# MA2400_P2_MODUAL.net
KiCad netlist of a schematic drawn in Altium Designer
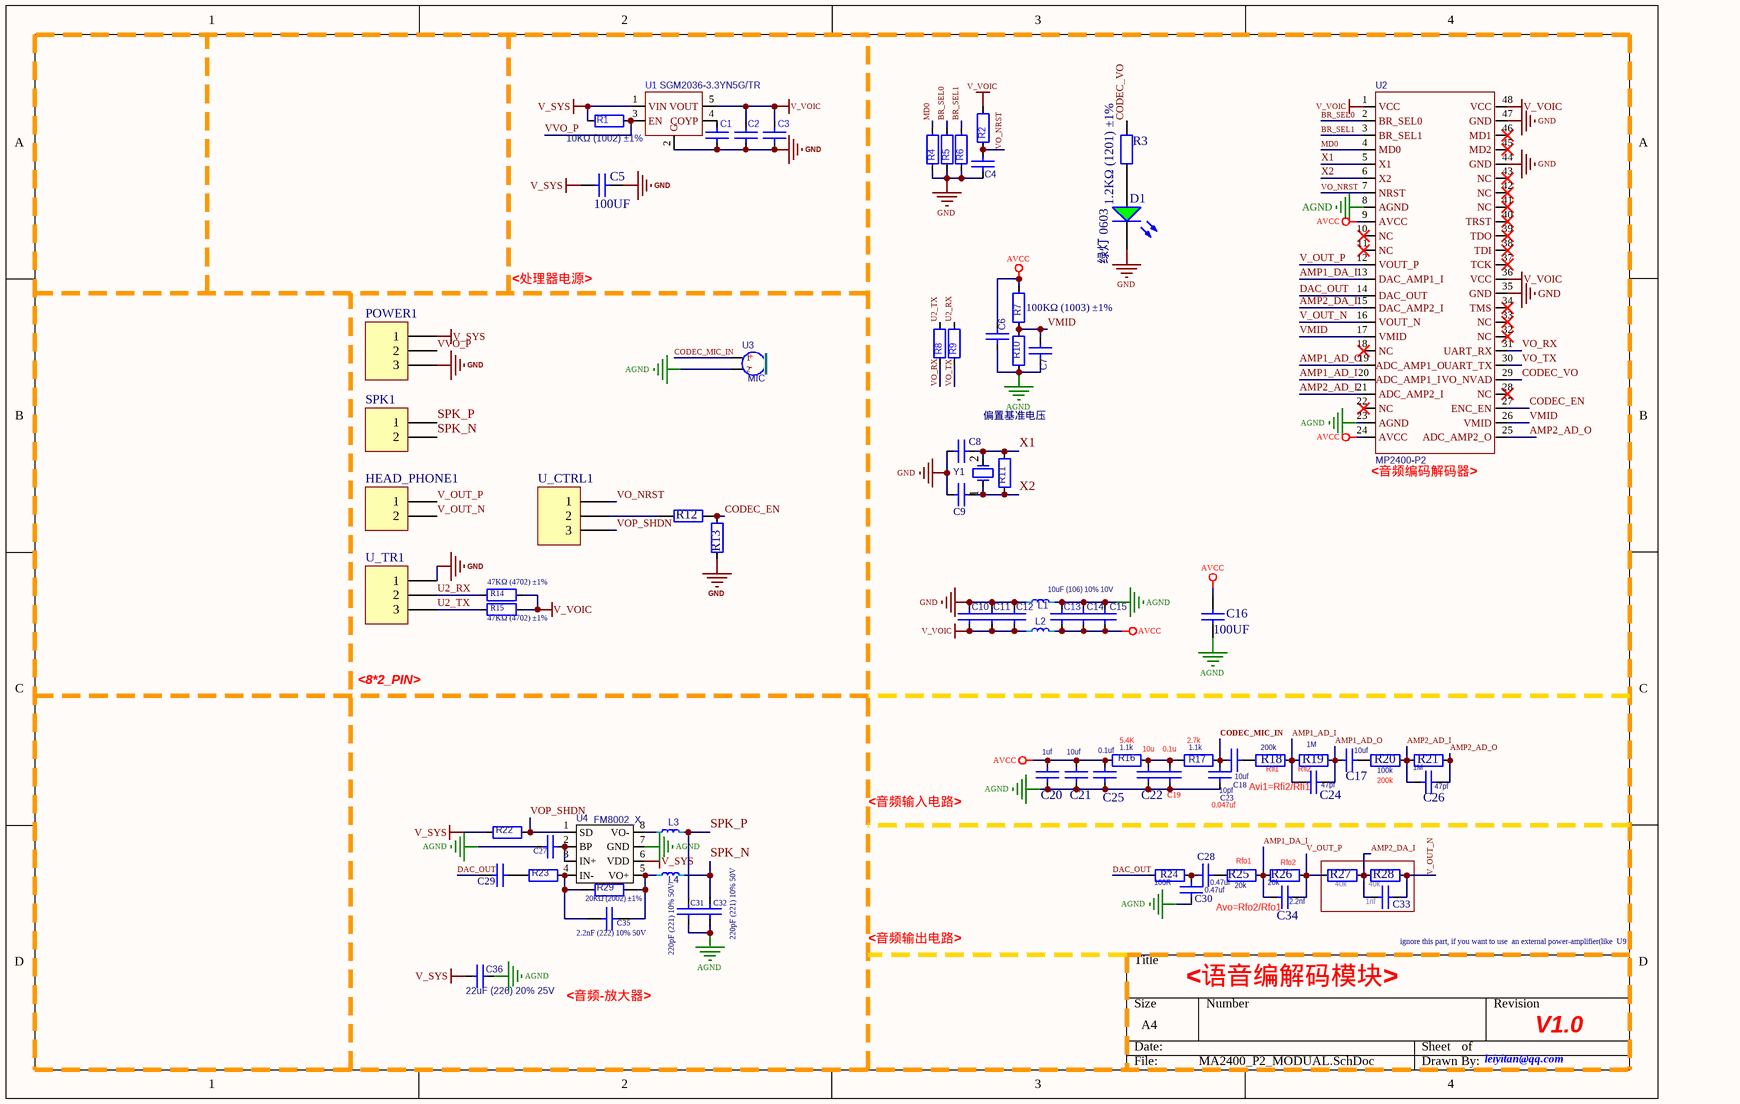
[diagram p0: MA2400_P2_MODUAL.SchDoc]

(export (version "E")
  (design (tool "Eeschema 10.0.6"))
  (components
    (comp (ref "C1")
      (value "100nF (104) 10% 16V")
      (footprint "0402_C")
      (description "贴片电容")
      (libsource (lib "Miscellaneous Devices LC") (part "0402 100nF (104) 10% 16V"))
    )
    (comp (ref "C2")
      (value "100nF (104) 10% 16V")
      (footprint "0402_C")
      (description "贴片电容")
      (libsource (lib "Miscellaneous Devices LC") (part "0402 100nF (104) 10% 16V"))
    )
    (comp (ref "C3")
      (value "10uF (106) 10% 10V")
      (footprint "0603_C")
      (description "贴片电容")
      (libsource (lib "Miscellaneous Devices LC") (part "0603 10uF (106) 10% 10V"))
    )
    (comp (ref "C4")
      (value "10uF (106) 20% 6.3V")
      (footprint "0402_C")
      (description "贴片电容")
      (libsource (lib "Miscellaneous Devices LC") (part "0402 10uF (106) 20% 6.3V"))
    )
    (comp (ref "C5")
      (value "100UF")
      (footprint "C1210")
      (description "贴片钽电容")
      (libsource (lib "Miscellaneous Devices LC") (part "1206 10uF (106) 10% 50V"))
    )
    (comp (ref "C6")
      (value "1.0uF (105) 10% 25V")
      (footprint "0402_C")
      (description "贴片电容")
      (libsource (lib "Miscellaneous Devices LC") (part "0402 1.0uF (105) 10% 25V"))
    )
    (comp (ref "C7")
      (value "1.0uF (105) 10% 25V")
      (footprint "0402_C")
      (description "贴片电容")
      (libsource (lib "Miscellaneous Devices LC") (part "0402 1.0uF (105) 10% 25V"))
    )
    (comp (ref "C8")
      (value "12pF (120) 5% 50V")
      (footprint "0603_C")
      (description "贴片电容")
      (libsource (lib "Miscellaneous Devices LC") (part "0603 12pF (120) 5% 50V"))
    )
    (comp (ref "C9")
      (value "12pF (120) 5% 50V")
      (footprint "0603_C")
      (description "贴片电容")
      (libsource (lib "Miscellaneous Devices LC") (part "0603 12pF (120) 5% 50V"))
    )
    (comp (ref "C10")
      (value "100nF (104) 10% 16V")
      (footprint "0402_C")
      (description "贴片电容")
      (libsource (lib "Miscellaneous Devices LC") (part "0402 100nF (104) 10% 16V"))
    )
    (comp (ref "C11")
      (value "100nF (104) 10% 16V")
      (footprint "0402_C")
      (description "贴片电容")
      (libsource (lib "Miscellaneous Devices LC") (part "0402 100nF (104) 10% 16V"))
    )
    (comp (ref "C12")
      (value "100nF (104) 10% 16V")
      (footprint "0402_C")
      (description "贴片电容")
      (libsource (lib "Miscellaneous Devices LC") (part "0402 100nF (104) 10% 16V"))
    )
    (comp (ref "C13")
      (value "10uF (106) 10% 10V")
      (footprint "0603_C")
      (description "贴片电容")
      (libsource (lib "Miscellaneous Devices LC") (part "0603 10uF (106) 10% 10V"))
    )
    (comp (ref "C14")
      (value "100nF (104) 10% 16V")
      (footprint "0402_C")
      (description "贴片电容")
      (libsource (lib "Miscellaneous Devices LC") (part "0402 100nF (104) 10% 16V"))
    )
    (comp (ref "C15")
      (value "100nF (104) 10% 16V")
      (footprint "0402_C")
      (description "贴片电容")
      (libsource (lib "Miscellaneous Devices LC") (part "0402 100nF (104) 10% 16V"))
    )
    (comp (ref "C16")
      (value "100UF")
      (footprint "C1210")
      (description "贴片钽电容")
      (libsource (lib "Miscellaneous Devices LC") (part "1206 10uF (106) 10% 50V"))
    )
    (comp (ref "C17")
      (value "10uF (106) 10% 25V")
      (footprint "0805_C")
      (description "贴片电容")
      (libsource (lib "Miscellaneous Devices LC") (part "0805 10uF (106) 10% 25V"))
    )
    (comp (ref "C18")
      (value "10uF (106) 10% 25V")
      (footprint "0805_C")
      (description "贴片电容")
      (libsource (lib "Miscellaneous Devices LC") (part "0805 10uF (106) 10% 25V"))
    )
    (comp (ref "C19")
      (value "47nF (473) 10% 50V")
      (footprint "0805_C")
      (description "贴片电容")
      (libsource (lib "Miscellaneous Devices LC") (part "0805 47nF (473) 10% 50V"))
    )
    (comp (ref "C20")
      (value "1uF (105) 10% 50V")
      (footprint "0805_C")
      (description "贴片电容")
      (libsource (lib "Miscellaneous Devices LC") (part "0805 1uF (105) 10% 50V"))
    )
    (comp (ref "C21")
      (value "10uF (106) 10% 25V")
      (footprint "0805_C")
      (description "贴片电容")
      (libsource (lib "Miscellaneous Devices LC") (part "0805 10uF (106) 10% 25V"))
    )
    (comp (ref "C22")
      (value "47nF (473) 10% 50V")
      (footprint "0805_C")
      (description "贴片电容")
      (libsource (lib "Miscellaneous Devices LC") (part "0805 47nF (473) 10% 50V"))
    )
    (comp (ref "C23")
      (value "10pF (100) 5% 50V")
      (footprint "0603_C")
      (description "贴片电容")
      (libsource (lib "Miscellaneous Devices LC") (part "0603 10pF (100) 5% 50V"))
    )
    (comp (ref "C24")
      (value "47pF (470) 5% 50V")
      (footprint "0805_C")
      (description "贴片电容")
      (libsource (lib "Miscellaneous Devices LC") (part "0805 47pF (470) 5% 50V"))
    )
    (comp (ref "C25")
      (value "100nF(104) 10% 50V")
      (footprint "0805_C")
      (description "贴片电容")
      (libsource (lib "Miscellaneous Devices LC") (part "0805 100nF(104) 10% 50V"))
    )
    (comp (ref "C26")
      (value "47pF (470) 5% 50V")
      (footprint "0805_C")
      (description "贴片电容")
      (libsource (lib "Miscellaneous Devices LC") (part "0805 47pF (470) 5% 50V"))
    )
    (comp (ref "C27")
      (value "1uF (105) 10% 50V")
      (footprint "0805_C")
      (description "贴片电容")
      (libsource (lib "Miscellaneous Devices LC") (part "0805 1uF (105) 10% 50V"))
    )
    (comp (ref "C28")
      (value "470nF (474) 10% 50V")
      (footprint "0805_C")
      (description "贴片电容")
      (libsource (lib "") (part "0805 470nF (474) 10% 50V_1"))
    )
    (comp (ref "C29")
      (value "470nF (474) 10% 50V")
      (footprint "0805_C")
      (description "贴片电容")
      (libsource (lib "Miscellaneous Devices LC") (part "0805 470nF (474) 10% 50V"))
    )
    (comp (ref "C30")
      (value "470nF (474) 10% 50V")
      (footprint "0805_C")
      (description "贴片电容")
      (libsource (lib "") (part "0805 470nF (474) 10% 50V_1"))
    )
    (comp (ref "C31")
      (value "220pF (221) 10% 50V")
      (footprint "0402_C")
      (description "贴片电容")
      (libsource (lib "Miscellaneous Devices LC") (part "0402 220pF (221) 10% 50V"))
    )
    (comp (ref "C32")
      (value "220pF (221) 10% 50V")
      (footprint "0402_C")
      (description "贴片电容")
      (libsource (lib "Miscellaneous Devices LC") (part "0402 220pF (221) 10% 50V"))
    )
    (comp (ref "C33")
      (value "1nF (102) 10% 50V")
      (footprint "0805_C")
      (description "贴片电容")
      (libsource (lib "Miscellaneous Devices LC") (part "0805 1nF (102) 10% 50V"))
    )
    (comp (ref "C34")
      (value "2.2nF (222) 5% 50V")
      (footprint "0805_C")
      (description "贴片电容")
      (libsource (lib "Miscellaneous Devices LC") (part "0805 2.2nF (222) 5% 50V"))
    )
    (comp (ref "C35")
      (value "2.2nF (222) 10% 50V")
      (footprint "0603_C")
      (description "贴片电容")
      (libsource (lib "Miscellaneous Devices LC") (part "0603 2.2nF (222) 10% 50V"))
    )
    (comp (ref "C36")
      (value "22uF (226) 20% 25V")
      (footprint "0805_C")
      (description "贴片电容")
      (libsource (lib "Miscellaneous Devices LC") (part "0805 22uF (226) 20% 25V"))
    )
    (comp (ref "D1")
      (value "绿灯 0603")
      (footprint "0603_LED_S1")
      (description "发光二极管")
      (libsource (lib "Miscellaneous Devices LC") (part "0603 绿灯"))
    )
    (comp (ref "HEAD_PHONE1")
      (value "~")
      (footprint "HDR1X2")
      (description "Header, 2-Pin")
      (fields (field (name "PUBLISHER") "Altium Limited"))
      (libsource (lib "Miscellaneous Connectors") (part "Header 2"))
    )
    (comp (ref "L1")
      (value "10uH ±10%")
      (footprint "0603_L")
      (description "贴片电感")
      (libsource (lib "ZGB_Sta_Prj") (part "BEAD"))
    )
    (comp (ref "L2")
      (value "10uH ±10%")
      (footprint "0603_L")
      (description "贴片电感")
      (libsource (lib "ZGB_Sta_Prj") (part "BEAD"))
    )
    (comp (ref "L3")
      (value "10uH ±10%")
      (footprint "0603_L")
      (description "贴片电感")
      (libsource (lib "ZGB_Sta_Prj") (part "BEAD"))
    )
    (comp (ref "L4")
      (value "10uH ±10%")
      (footprint "0603_L")
      (description "贴片电感")
      (libsource (lib "ZGB_Sta_Prj") (part "BEAD"))
    )
    (comp (ref "POWER1")
      (value "~")
      (footprint "HDR1X3")
      (description "Header, 3-Pin")
      (fields (field (name "PUBLISHER") "Altium Limited"))
      (libsource (lib "Miscellaneous Connectors") (part "Header 3"))
    )
    (comp (ref "R1")
      (value "10KΩ (1002) ±1%")
      (footprint "0402_R")
      (description "贴片电阻")
      (libsource (lib "") (part "0402 10KΩ (1002) 1%_2"))
    )
    (comp (ref "R2")
      (value "10KΩ (1002) ±1%")
      (footprint "0402_R")
      (description "贴片电阻")
      (libsource (lib "Miscellaneous Devices LC") (part "0402 10KΩ (1002) 1%"))
    )
    (comp (ref "R3")
      (value "1.2KΩ (1201) ±1%")
      (footprint "0402_R")
      (description "贴片电阻")
      (libsource (lib "Miscellaneous Devices LC") (part "0402 1.2KΩ (1201) 1%"))
    )
    (comp (ref "R4")
      (value "10KΩ (1002) ±1%")
      (footprint "0402_R")
      (description "贴片电阻")
      (libsource (lib "Miscellaneous Devices LC") (part "0402 10KΩ (1002) 1%"))
    )
    (comp (ref "R5")
      (value "10KΩ (1002) ±1%")
      (footprint "0402_R")
      (description "贴片电阻")
      (libsource (lib "Miscellaneous Devices LC") (part "0402 10KΩ (1002) 1%"))
    )
    (comp (ref "R6")
      (value "10KΩ (1002) ±1%")
      (footprint "0402_R")
      (description "贴片电阻")
      (libsource (lib "Miscellaneous Devices LC") (part "0402 10KΩ (1002) 1%"))
    )
    (comp (ref "R7")
      (value "100KΩ (1003) ±1%")
      (footprint "0402_R")
      (description "贴片电阻")
      (libsource (lib "Miscellaneous Devices LC") (part "0402 100KΩ (1003) 1%"))
    )
    (comp (ref "R8")
      (value "10KΩ (1002) ±1%")
      (footprint "0402_R")
      (description "贴片电阻")
      (libsource (lib "Miscellaneous Devices LC") (part "0402 10KΩ (1002) 1%"))
    )
    (comp (ref "R9")
      (value "10KΩ (1002) ±1%")
      (footprint "0402_R")
      (description "贴片电阻")
      (libsource (lib "Miscellaneous Devices LC") (part "0402 10KΩ (1002) 1%"))
    )
    (comp (ref "R10")
      (value "100KΩ (1003) ±1%")
      (footprint "0402_R")
      (description "贴片电阻")
      (libsource (lib "Miscellaneous Devices LC") (part "0402 100KΩ (1003) 1%"))
    )
    (comp (ref "R11")
      (value "1MΩ (1004) ±1%")
      (footprint "0402_R")
      (description "贴片电阻")
      (libsource (lib "Miscellaneous Devices LC") (part "0402 1MΩ (1004) 1%"))
    )
    (comp (ref "R12")
      (value "1KΩ (1001) ±1%")
      (footprint "0402_R")
      (description "贴片电阻")
      (libsource (lib "Miscellaneous Devices LC") (part "0402 1KΩ (1001) 1%"))
    )
    (comp (ref "R13")
      (value "10KΩ (1002) ±1%")
      (footprint "0402_R")
      (description "贴片电阻")
      (libsource (lib "") (part "0402 10KΩ (1002) 1%_1"))
    )
    (comp (ref "R14")
      (value "47KΩ (4702) ±1%")
      (footprint "0402_R")
      (description "贴片电阻")
      (libsource (lib "Miscellaneous Devices LC") (part "0402 47KΩ (4702) 1%"))
    )
    (comp (ref "R15")
      (value "47KΩ (4702) ±1%")
      (footprint "0402_R")
      (description "贴片电阻")
      (libsource (lib "Miscellaneous Devices LC") (part "0402 47KΩ (4702) 1%"))
    )
    (comp (ref "R16")
      (value "1.1KΩ (1101) ±1%")
      (footprint "0603_R")
      (description "贴片电阻")
      (libsource (lib "Miscellaneous Devices LC") (part "0603 1.1KΩ (1101) 1%"))
    )
    (comp (ref "R17")
      (value "1.1KΩ (1101) ±1%")
      (footprint "0603_R")
      (description "贴片电阻")
      (libsource (lib "Miscellaneous Devices LC") (part "0603 1.1KΩ (1101) 1%"))
    )
    (comp (ref "R18")
      (value "200KΩ (2003) ±1%")
      (footprint "0805_R")
      (description "贴片电阻")
      (libsource (lib "Miscellaneous Devices LC") (part "0805 200KΩ (2003) 1%"))
    )
    (comp (ref "R19")
      (value "1MΩ (1004) ±1%")
      (footprint "0805_R")
      (description "贴片电阻")
      (libsource (lib "Miscellaneous Devices LC") (part "0805 1MΩ (1004) 1%"))
    )
    (comp (ref "R20")
      (value "100KΩ (1003) ±1%")
      (footprint "0805_R")
      (description "贴片电阻")
      (libsource (lib "Miscellaneous Devices LC") (part "0805 100KΩ (1003) 1%"))
    )
    (comp (ref "R21")
      (value "1MΩ (1004) ±1%")
      (footprint "0805_R")
      (description "贴片电阻")
      (libsource (lib "Miscellaneous Devices LC") (part "0805 1MΩ (1004) 1%"))
    )
    (comp (ref "R22")
      (value "10KΩ (1002) ±1%")
      (footprint "0402_R")
      (description "贴片电阻")
      (libsource (lib "") (part "0402 10KΩ (1002) 1%_2"))
    )
    (comp (ref "R23")
      (value "20KΩ (2002) ±1%")
      (footprint "0402_R")
      (description "贴片电阻")
      (libsource (lib "") (part "0402 20KΩ (2002) 1%_1"))
    )
    (comp (ref "R24")
      (value "100Ω (1000) ±1%")
      (footprint "0805_R")
      (description "贴片电阻")
      (libsource (lib "Miscellaneous Devices LC") (part "0805 100Ω (1000) 1%"))
    )
    (comp (ref "R25")
      (value "20KΩ (2002) ±1%")
      (footprint "0805_R")
      (description "贴片电阻")
      (libsource (lib "Miscellaneous Devices LC") (part "0805 20KΩ (2002) 1%"))
    )
    (comp (ref "R26")
      (value "20KΩ (2002) ±1%")
      (footprint "0805_R")
      (description "贴片电阻")
      (libsource (lib "Miscellaneous Devices LC") (part "0805 20KΩ (2002) 1%"))
    )
    (comp (ref "R27")
      (value "40.2KΩ (4022) ±1%")
      (footprint "0805_R")
      (description "贴片电阻")
      (libsource (lib "Miscellaneous Devices LC") (part "0805 40.2KΩ (4022) 1%"))
    )
    (comp (ref "R28")
      (value "40.2KΩ (4022) ±1%")
      (footprint "0805_R")
      (description "贴片电阻")
      (libsource (lib "Miscellaneous Devices LC") (part "0805 40.2KΩ (4022) 1%"))
    )
    (comp (ref "R29")
      (value "20KΩ (2002) ±1%")
      (footprint "0402_R")
      (description "贴片电阻")
      (libsource (lib "Miscellaneous Devices LC") (part "0402 20KΩ (2002) 1%"))
    )
    (comp (ref "SPK1")
      (value "~")
      (footprint "HDR1X2")
      (description "Header, 2-Pin")
      (fields (field (name "PUBLISHER") "Altium Limited"))
      (libsource (lib "Miscellaneous Connectors") (part "Header 2"))
    )
    (comp (ref "U1")
      (value "SGM2036-3.3YN5G/TR")
      (footprint "SOT23-5")
      (description "3.3 LDO")
      (libsource (lib "ZGB_Sta_Prj") (part "LDO"))
    )
    (comp (ref "U2")
      (value "MP2400-P2")
      (footprint "LQFP-48_7x7x05P")
      (description "音频处理器")
      (libsource (lib "ZGB_Sta_Prj") (part "MP2400-P2"))
    )
    (comp (ref "U3")
      (value "MIC")
      (footprint "6022_MIC")
      (description "6022插针七级防水咪头7级防水麦克风咪头")
      (libsource (lib "ZGB_Sta_Prj") (part "MIC"))
    )
    (comp (ref "U4")
      (value "FM8002_X")
      (footprint "SOP-8_150mil")
      (description "音频放大器")
      (libsource (lib "ZGB_Sta_Prj") (part "FM8002_X"))
    )
    (comp (ref "U_CTRL1")
      (value "~")
      (footprint "HDR1X3")
      (description "Header, 3-Pin")
      (fields (field (name "PUBLISHER") "Altium Limited"))
      (libsource (lib "Miscellaneous Connectors") (part "Header 3"))
    )
    (comp (ref "U_TR1")
      (value "~")
      (footprint "HDR1X3")
      (description "Header, 3-Pin")
      (fields (field (name "PUBLISHER") "Altium Limited"))
      (libsource (lib "Miscellaneous Connectors") (part "Header 3"))
    )
    (comp (ref "Y1")
      (value "8MHz ±20ppm 20pF")
      (footprint "SMD-5032_2P")
      (description "贴片无源晶振/YSX530GA 8MHZ 20PF 10PPM -40~+85 编带")
      (libsource (lib "Miscellaneous Devices LC") (part "SMD-5032_2P 8MHz 20ppm 20pF"))
    )
  )
  (nets
    (net (code "1") (name "/AMP1_AD_I") (class "Default")
      (node (ref "C24") (pin "1") (pinfunction "1_1") (pintype "passive"))
      (node (ref "R18") (pin "2") (pinfunction "2_2") (pintype "passive"))
      (node (ref "R19") (pin "1") (pinfunction "1_1") (pintype "passive"))
      (node (ref "U2") (pin "20") (pinfunction "ADC_AMP1_I_20") (pintype "passive"))
    )
    (net (code "2") (name "/AMP1_AD_O") (class "Default")
      (node (ref "C17") (pin "2") (pinfunction "2_2") (pintype "passive"))
      (node (ref "C24") (pin "2") (pinfunction "2_2") (pintype "passive"))
      (node (ref "R19") (pin "2") (pinfunction "2_2") (pintype "passive"))
      (node (ref "U2") (pin "19") (pinfunction "ADC_AMP1_O_19") (pintype "passive"))
    )
    (net (code "3") (name "/AMP1_DA_I") (class "Default")
      (node (ref "C34") (pin "2") (pinfunction "2_2") (pintype "passive"))
      (node (ref "R25") (pin "2") (pinfunction "2_2") (pintype "passive"))
      (node (ref "R26") (pin "1") (pinfunction "1_1") (pintype "passive"))
      (node (ref "U2") (pin "13") (pinfunction "DAC_AMP1_I_13") (pintype "passive"))
    )
    (net (code "4") (name "/AMP2_AD_I") (class "Default")
      (node (ref "C26") (pin "1") (pinfunction "1_1") (pintype "passive"))
      (node (ref "R20") (pin "2") (pinfunction "2_2") (pintype "passive"))
      (node (ref "R21") (pin "1") (pinfunction "1_1") (pintype "passive"))
      (node (ref "U2") (pin "21") (pinfunction "ADC_AMP2_I_21") (pintype "passive"))
    )
    (net (code "5") (name "/AMP2_AD_O") (class "Default")
      (node (ref "C26") (pin "2") (pinfunction "2_2") (pintype "passive"))
      (node (ref "R21") (pin "2") (pinfunction "2_2") (pintype "passive"))
      (node (ref "U2") (pin "25") (pinfunction "ADC_AMP2_O_25") (pintype "passive"))
    )
    (net (code "6") (name "/AMP2_DA_I") (class "Default")
      (node (ref "C33") (pin "1") (pinfunction "1_1") (pintype "passive"))
      (node (ref "R27") (pin "2") (pinfunction "2_2") (pintype "passive"))
      (node (ref "R28") (pin "1") (pinfunction "1_1") (pintype "passive"))
      (node (ref "U2") (pin "15") (pinfunction "DAC_AMP2_I_15") (pintype "passive"))
    )
    (net (code "7") (name "/BR_SEL0") (class "Default")
      (node (ref "R5") (pin "2") (pinfunction "2_2") (pintype "passive"))
      (node (ref "U2") (pin "2") (pinfunction "BR_SEL0_2") (pintype "passive"))
    )
    (net (code "8") (name "/BR_SEL1") (class "Default")
      (node (ref "R6") (pin "2") (pinfunction "2_2") (pintype "passive"))
      (node (ref "U2") (pin "3") (pinfunction "BR_SEL1_3") (pintype "passive"))
    )
    (net (code "9") (name "/CODEC_EN") (class "Default")
      (node (ref "R12") (pin "2") (pinfunction "2_2") (pintype "passive"))
      (node (ref "R13") (pin "1") (pinfunction "1_1") (pintype "passive"))
      (node (ref "U2") (pin "27") (pinfunction "ENC_EN_27") (pintype "passive"))
    )
    (net (code "10") (name "/CODEC_MIC_IN") (class "Default")
      (node (ref "C18") (pin "2") (pinfunction "2_2") (pintype "passive"))
      (node (ref "C23") (pin "2") (pinfunction "2_2") (pintype "passive"))
      (node (ref "R17") (pin "2") (pinfunction "2_2") (pintype "passive"))
      (node (ref "U3") (pin "1") (pinfunction "1_1") (pintype "passive"))
    )
    (net (code "11") (name "/CODEC_VO") (class "Default")
      (node (ref "R3") (pin "2") (pinfunction "2_2") (pintype "passive"))
      (node (ref "U2") (pin "29") (pinfunction "VO_NVAD_29") (pintype "passive"))
    )
    (net (code "12") (name "/DAC_OUT") (class "Default")
      (node (ref "C29") (pin "1") (pinfunction "1_1") (pintype "passive"))
      (node (ref "R24") (pin "1") (pinfunction "1_1") (pintype "passive"))
      (node (ref "U2") (pin "14") (pinfunction "DAC_OUT_14") (pintype "passive"))
    )
    (net (code "13") (name "/MD0") (class "Default")
      (node (ref "R4") (pin "2") (pinfunction "2_2") (pintype "passive"))
      (node (ref "U2") (pin "4") (pinfunction "MD0_4") (pintype "passive"))
    )
    (net (code "14") (name "/SPK_N") (class "Default")
      (node (ref "C32") (pin "2") (pinfunction "2_2") (pintype "passive"))
      (node (ref "L4") (pin "1") (pinfunction "1_1") (pintype "passive"))
      (node (ref "SPK1") (pin "2") (pinfunction "2_2") (pintype "passive"))
    )
    (net (code "15") (name "/SPK_P") (class "Default")
      (node (ref "C31") (pin "2") (pinfunction "2_2") (pintype "passive"))
      (node (ref "L3") (pin "1") (pinfunction "1_1") (pintype "passive"))
      (node (ref "SPK1") (pin "1") (pinfunction "1_1") (pintype "passive"))
    )
    (net (code "16") (name "/U2_RX") (class "Default")
      (node (ref "R14") (pin "1") (pinfunction "1_1") (pintype "passive"))
      (node (ref "R9") (pin "2") (pinfunction "2_2") (pintype "passive"))
      (node (ref "U_TR1") (pin "2") (pinfunction "2_2") (pintype "passive"))
    )
    (net (code "17") (name "/U2_TX") (class "Default")
      (node (ref "R15") (pin "1") (pinfunction "1_1") (pintype "passive"))
      (node (ref "R8") (pin "2") (pinfunction "2_2") (pintype "passive"))
      (node (ref "U_TR1") (pin "3") (pinfunction "3_3") (pintype "passive"))
    )
    (net (code "18") (name "/VMID") (class "Default")
      (node (ref "C7") (pin "2") (pinfunction "2_2") (pintype "passive"))
      (node (ref "R10") (pin "2") (pinfunction "2_2") (pintype "passive"))
      (node (ref "R7") (pin "1") (pinfunction "1_1") (pintype "passive"))
      (node (ref "U2") (pin "17") (pinfunction "VMID_17") (pintype "passive"))
      (node (ref "U2") (pin "26") (pinfunction "VMID_26") (pintype "passive"))
    )
    (net (code "19") (name "/VOP_SHDN") (class "Default")
      (node (ref "R22") (pin "2") (pinfunction "2_2") (pintype "passive"))
      (node (ref "U4") (pin "1") (pinfunction "SD_1") (pintype "passive"))
      (node (ref "U_CTRL1") (pin "3") (pinfunction "3_3") (pintype "passive"))
    )
    (net (code "20") (name "/VO_NRST") (class "Default")
      (node (ref "C4") (pin "2") (pinfunction "2_2") (pintype "passive"))
      (node (ref "R2") (pin "1") (pinfunction "1_1") (pintype "passive"))
      (node (ref "U2") (pin "7") (pinfunction "NRST_7") (pintype "passive"))
      (node (ref "U_CTRL1") (pin "1") (pinfunction "1_1") (pintype "passive"))
    )
    (net (code "21") (name "/VO_RX") (class "Default")
      (node (ref "R8") (pin "1") (pinfunction "1_1") (pintype "passive"))
      (node (ref "U2") (pin "31") (pinfunction "UART_RX_31") (pintype "passive"))
    )
    (net (code "22") (name "/VO_TX") (class "Default")
      (node (ref "R9") (pin "1") (pinfunction "1_1") (pintype "passive"))
      (node (ref "U2") (pin "30") (pinfunction "UART_TX_30") (pintype "passive"))
    )
    (net (code "23") (name "/VVO_P") (class "Default")
      (node (ref "POWER1") (pin "2") (pinfunction "2_2") (pintype "passive"))
      (node (ref "R1") (pin "2") (pinfunction "2_2") (pintype "passive"))
      (node (ref "U1") (pin "3") (pinfunction "EN_3") (pintype "passive"))
    )
    (net (code "24") (name "/V_OUT_N") (class "Default")
      (node (ref "C33") (pin "2") (pinfunction "2_2") (pintype "passive"))
      (node (ref "HEAD_PHONE1") (pin "2") (pinfunction "2_2") (pintype "passive"))
      (node (ref "R28") (pin "2") (pinfunction "2_2") (pintype "passive"))
      (node (ref "U2") (pin "16") (pinfunction "VOUT_N_16") (pintype "passive"))
    )
    (net (code "25") (name "/V_OUT_P") (class "Default")
      (node (ref "C34") (pin "1") (pinfunction "1_1") (pintype "passive"))
      (node (ref "HEAD_PHONE1") (pin "1") (pinfunction "1_1") (pintype "passive"))
      (node (ref "R26") (pin "2") (pinfunction "2_2") (pintype "passive"))
      (node (ref "R27") (pin "1") (pinfunction "1_1") (pintype "passive"))
      (node (ref "U2") (pin "12") (pinfunction "VOUT_P_12") (pintype "passive"))
    )
    (net (code "26") (name "/X1") (class "Default")
      (node (ref "C8") (pin "2") (pinfunction "2_2") (pintype "passive"))
      (node (ref "R11") (pin "2") (pinfunction "2_2") (pintype "passive"))
      (node (ref "U2") (pin "5") (pinfunction "X1_5") (pintype "passive"))
      (node (ref "Y1") (pin "2") (pinfunction "OSC2_2") (pintype "passive"))
    )
    (net (code "27") (name "/X2") (class "Default")
      (node (ref "C9") (pin "1") (pinfunction "1_1") (pintype "passive"))
      (node (ref "R11") (pin "1") (pinfunction "1_1") (pintype "passive"))
      (node (ref "U2") (pin "6") (pinfunction "X2_6") (pintype "passive"))
      (node (ref "Y1") (pin "1") (pinfunction "OSC1_1") (pintype "passive"))
    )
    (net (code "28") (name "AGND") (class "Default")
      (node (ref "C13") (pin "2") (pinfunction "2_2") (pintype "passive"))
      (node (ref "C14") (pin "2") (pinfunction "2_2") (pintype "passive"))
      (node (ref "C15") (pin "2") (pinfunction "2_2") (pintype "passive"))
      (node (ref "C16") (pin "1") (pinfunction "1_1") (pintype "passive"))
      (node (ref "C19") (pin "1") (pinfunction "1_1") (pintype "passive"))
      (node (ref "C20") (pin "1") (pinfunction "1_1") (pintype "passive"))
      (node (ref "C21") (pin "1") (pinfunction "1_1") (pintype "passive"))
      (node (ref "C22") (pin "1") (pinfunction "1_1") (pintype "passive"))
      (node (ref "C23") (pin "1") (pinfunction "1_1") (pintype "passive"))
      (node (ref "C25") (pin "1") (pinfunction "1_1") (pintype "passive"))
      (node (ref "C27") (pin "1") (pinfunction "1_1") (pintype "passive"))
      (node (ref "C30") (pin "1") (pinfunction "1_1") (pintype "passive"))
      (node (ref "C31") (pin "1") (pinfunction "1_1") (pintype "passive"))
      (node (ref "C32") (pin "1") (pinfunction "1_1") (pintype "passive"))
      (node (ref "C36") (pin "2") (pinfunction "2_2") (pintype "passive"))
      (node (ref "C6") (pin "1") (pinfunction "1_1") (pintype "passive"))
      (node (ref "C7") (pin "1") (pinfunction "1_1") (pintype "passive"))
      (node (ref "L1") (pin "1") (pinfunction "1_1") (pintype "passive"))
      (node (ref "R10") (pin "1") (pinfunction "1_1") (pintype "passive"))
      (node (ref "U2") (pin "23") (pinfunction "AGND_23") (pintype "passive"))
      (node (ref "U2") (pin "8") (pinfunction "AGND_8") (pintype "passive"))
      (node (ref "U3") (pin "2") (pinfunction "2_2") (pintype "passive"))
      (node (ref "U4") (pin "7") (pinfunction "GND_7") (pintype "passive"))
    )
    (net (code "29") (name "AVCC") (class "Default")
      (node (ref "C13") (pin "1") (pinfunction "1_1") (pintype "passive"))
      (node (ref "C14") (pin "1") (pinfunction "1_1") (pintype "passive"))
      (node (ref "C15") (pin "1") (pinfunction "1_1") (pintype "passive"))
      (node (ref "C16") (pin "2") (pinfunction "2_2") (pintype "passive"))
      (node (ref "C20") (pin "2") (pinfunction "2_2") (pintype "passive"))
      (node (ref "C21") (pin "2") (pinfunction "2_2") (pintype "passive"))
      (node (ref "C25") (pin "2") (pinfunction "2_2") (pintype "passive"))
      (node (ref "C6") (pin "2") (pinfunction "2_2") (pintype "passive"))
      (node (ref "L2") (pin "1") (pinfunction "1_1") (pintype "passive"))
      (node (ref "R16") (pin "1") (pinfunction "1_1") (pintype "passive"))
      (node (ref "R7") (pin "2") (pinfunction "2_2") (pintype "passive"))
      (node (ref "U2") (pin "24") (pinfunction "AVCC_24") (pintype "passive"))
      (node (ref "U2") (pin "9") (pinfunction "AVCC_9") (pintype "passive"))
    )
    (net (code "30") (name "GND") (class "Default")
      (node (ref "C1") (pin "1") (pinfunction "1_1") (pintype "passive"))
      (node (ref "C10") (pin "2") (pinfunction "2_2") (pintype "passive"))
      (node (ref "C11") (pin "2") (pinfunction "2_2") (pintype "passive"))
      (node (ref "C12") (pin "2") (pinfunction "2_2") (pintype "passive"))
      (node (ref "C2") (pin "1") (pinfunction "1_1") (pintype "passive"))
      (node (ref "C3") (pin "1") (pinfunction "1_1") (pintype "passive"))
      (node (ref "C4") (pin "1") (pinfunction "1_1") (pintype "passive"))
      (node (ref "C5") (pin "2") (pinfunction "2_2") (pintype "passive"))
      (node (ref "C8") (pin "1") (pinfunction "1_1") (pintype "passive"))
      (node (ref "C9") (pin "2") (pinfunction "2_2") (pintype "passive"))
      (node (ref "D1") (pin "K") (pinfunction "K_K") (pintype "passive"))
      (node (ref "L1") (pin "2") (pinfunction "2_2") (pintype "passive"))
      (node (ref "POWER1") (pin "3") (pinfunction "3_3") (pintype "passive"))
      (node (ref "R13") (pin "2") (pinfunction "2_2") (pintype "passive"))
      (node (ref "R4") (pin "1") (pinfunction "1_1") (pintype "passive"))
      (node (ref "R5") (pin "1") (pinfunction "1_1") (pintype "passive"))
      (node (ref "R6") (pin "1") (pinfunction "1_1") (pintype "passive"))
      (node (ref "U1") (pin "2") (pinfunction "G_2") (pintype "passive"))
      (node (ref "U2") (pin "35") (pinfunction "GND_35") (pintype "passive"))
      (node (ref "U2") (pin "44") (pinfunction "GND_44") (pintype "passive"))
      (node (ref "U2") (pin "47") (pinfunction "GND_47") (pintype "passive"))
      (node (ref "U_TR1") (pin "1") (pinfunction "1_1") (pintype "passive"))
    )
    (net (code "31") (name "Net-(C17-Pad1)") (class "Default")
      (node (ref "C17") (pin "1") (pinfunction "1_1") (pintype "passive"))
      (node (ref "R20") (pin "1") (pinfunction "1_1") (pintype "passive"))
    )
    (net (code "32") (name "Net-(C18-Pad1)") (class "Default")
      (node (ref "C18") (pin "1") (pinfunction "1_1") (pintype "passive"))
      (node (ref "R18") (pin "1") (pinfunction "1_1") (pintype "passive"))
    )
    (net (code "33") (name "Net-(C19-Pad2)") (class "Default")
      (node (ref "C19") (pin "2") (pinfunction "2_2") (pintype "passive"))
      (node (ref "C22") (pin "2") (pinfunction "2_2") (pintype "passive"))
      (node (ref "R16") (pin "2") (pinfunction "2_2") (pintype "passive"))
      (node (ref "R17") (pin "1") (pinfunction "1_1") (pintype "passive"))
    )
    (net (code "34") (name "Net-(C28-Pad1)") (class "Default")
      (node (ref "C28") (pin "1") (pinfunction "1_1") (pintype "passive"))
      (node (ref "C30") (pin "2") (pinfunction "2_2") (pintype "passive"))
      (node (ref "R24") (pin "2") (pinfunction "2_2") (pintype "passive"))
    )
    (net (code "35") (name "Net-(C28-Pad2)") (class "Default")
      (node (ref "C28") (pin "2") (pinfunction "2_2") (pintype "passive"))
      (node (ref "R25") (pin "1") (pinfunction "1_1") (pintype "passive"))
    )
    (net (code "36") (name "Net-(C29-Pad2)") (class "Default")
      (node (ref "C29") (pin "2") (pinfunction "2_2") (pintype "passive"))
      (node (ref "R23") (pin "1") (pinfunction "1_1") (pintype "passive"))
    )
    (net (code "37") (name "Net-(D1-PadA)") (class "Default")
      (node (ref "D1") (pin "A") (pinfunction "A_A") (pintype "passive"))
      (node (ref "R3") (pin "1") (pinfunction "1_1") (pintype "passive"))
    )
    (net (code "38") (name "Net-(R12-Pad1)") (class "Default")
      (node (ref "R12") (pin "1") (pinfunction "1_1") (pintype "passive"))
      (node (ref "U_CTRL1") (pin "2") (pinfunction "2_2") (pintype "passive"))
    )
    (net (code "39") (name "Net-(U1-COYP)") (class "Default")
      (node (ref "C1") (pin "2") (pinfunction "2_2") (pintype "passive"))
      (node (ref "U1") (pin "4") (pinfunction "COYP_4") (pintype "passive"))
    )
    (net (code "40") (name "Net-(U4-BP)") (class "Default")
      (node (ref "C27") (pin "2") (pinfunction "2_2") (pintype "passive"))
      (node (ref "U4") (pin "2") (pinfunction "BP_2") (pintype "passive"))
      (node (ref "U4") (pin "3") (pinfunction "IN+_3") (pintype "passive"))
    )
    (net (code "41") (name "Net-(U4-IN-)") (class "Default")
      (node (ref "C35") (pin "1") (pinfunction "1_1") (pintype "passive"))
      (node (ref "R23") (pin "2") (pinfunction "2_2") (pintype "passive"))
      (node (ref "R29") (pin "1") (pinfunction "1_1") (pintype "passive"))
      (node (ref "U4") (pin "4") (pinfunction "IN-_4") (pintype "passive"))
    )
    (net (code "42") (name "Net-(U4-VO+)") (class "Default")
      (node (ref "C35") (pin "2") (pinfunction "2_2") (pintype "passive"))
      (node (ref "L4") (pin "2") (pinfunction "2_2") (pintype "passive"))
      (node (ref "R29") (pin "2") (pinfunction "2_2") (pintype "passive"))
      (node (ref "U4") (pin "5") (pinfunction "VO+_5") (pintype "passive"))
    )
    (net (code "43") (name "Net-(U4-VO-)") (class "Default")
      (node (ref "L3") (pin "2") (pinfunction "2_2") (pintype "passive"))
      (node (ref "U4") (pin "8") (pinfunction "VO-_8") (pintype "passive"))
    )
    (net (code "44") (name "V_SYS") (class "Default")
      (node (ref "C36") (pin "1") (pinfunction "1_1") (pintype "passive"))
      (node (ref "C5") (pin "1") (pinfunction "1_1") (pintype "passive"))
      (node (ref "POWER1") (pin "1") (pinfunction "1_1") (pintype "passive"))
      (node (ref "R1") (pin "1") (pinfunction "1_1") (pintype "passive"))
      (node (ref "R22") (pin "1") (pinfunction "1_1") (pintype "passive"))
      (node (ref "U1") (pin "1") (pinfunction "VIN_1") (pintype "passive"))
      (node (ref "U4") (pin "6") (pinfunction "VDD_6") (pintype "passive"))
    )
    (net (code "45") (name "V_VOIC") (class "Default")
      (node (ref "C10") (pin "1") (pinfunction "1_1") (pintype "passive"))
      (node (ref "C11") (pin "1") (pinfunction "1_1") (pintype "passive"))
      (node (ref "C12") (pin "1") (pinfunction "1_1") (pintype "passive"))
      (node (ref "C2") (pin "2") (pinfunction "2_2") (pintype "passive"))
      (node (ref "C3") (pin "2") (pinfunction "2_2") (pintype "passive"))
      (node (ref "L2") (pin "2") (pinfunction "2_2") (pintype "passive"))
      (node (ref "R14") (pin "2") (pinfunction "2_2") (pintype "passive"))
      (node (ref "R15") (pin "2") (pinfunction "2_2") (pintype "passive"))
      (node (ref "R2") (pin "2") (pinfunction "2_2") (pintype "passive"))
      (node (ref "U1") (pin "5") (pinfunction "VOUT_5") (pintype "passive"))
      (node (ref "U2") (pin "1") (pinfunction "VCC_1") (pintype "passive"))
      (node (ref "U2") (pin "36") (pinfunction "VCC_36") (pintype "passive"))
      (node (ref "U2") (pin "48") (pinfunction "VCC_48") (pintype "passive"))
    )
    (net (code "46") (name "unconnected-(U2-MD1-Pad46)") (class "Default")
      (node (ref "U2") (pin "46") (pinfunction "MD1_46") (pintype "passive+no_connect"))
    )
    (net (code "47") (name "unconnected-(U2-MD2-Pad45)") (class "Default")
      (node (ref "U2") (pin "45") (pinfunction "MD2_45") (pintype "passive+no_connect"))
    )
    (net (code "48") (name "unconnected-(U2-NC-Pad10)") (class "Default")
      (node (ref "U2") (pin "10") (pinfunction "NC_10") (pintype "passive+no_connect"))
    )
    (net (code "49") (name "unconnected-(U2-NC-Pad11)") (class "Default")
      (node (ref "U2") (pin "11") (pinfunction "NC_11") (pintype "passive+no_connect"))
    )
    (net (code "50") (name "unconnected-(U2-NC-Pad18)") (class "Default")
      (node (ref "U2") (pin "18") (pinfunction "NC_18") (pintype "passive+no_connect"))
    )
    (net (code "51") (name "unconnected-(U2-NC-Pad22)") (class "Default")
      (node (ref "U2") (pin "22") (pinfunction "NC_22") (pintype "passive+no_connect"))
    )
    (net (code "52") (name "unconnected-(U2-NC-Pad28)") (class "Default")
      (node (ref "U2") (pin "28") (pinfunction "NC_28") (pintype "passive"))
    )
    (net (code "53") (name "unconnected-(U2-NC-Pad32)") (class "Default")
      (node (ref "U2") (pin "32") (pinfunction "NC_32") (pintype "passive+no_connect"))
    )
    (net (code "54") (name "unconnected-(U2-NC-Pad33)") (class "Default")
      (node (ref "U2") (pin "33") (pinfunction "NC_33") (pintype "passive+no_connect"))
    )
    (net (code "55") (name "unconnected-(U2-NC-Pad41)") (class "Default")
      (node (ref "U2") (pin "41") (pinfunction "NC_41") (pintype "passive+no_connect"))
    )
    (net (code "56") (name "unconnected-(U2-NC-Pad42)") (class "Default")
      (node (ref "U2") (pin "42") (pinfunction "NC_42") (pintype "passive+no_connect"))
    )
    (net (code "57") (name "unconnected-(U2-NC-Pad43)") (class "Default")
      (node (ref "U2") (pin "43") (pinfunction "NC_43") (pintype "passive+no_connect"))
    )
    (net (code "58") (name "unconnected-(U2-TCK-Pad37)") (class "Default")
      (node (ref "U2") (pin "37") (pinfunction "TCK_37") (pintype "passive+no_connect"))
    )
    (net (code "59") (name "unconnected-(U2-TDI-Pad38)") (class "Default")
      (node (ref "U2") (pin "38") (pinfunction "TDI_38") (pintype "passive+no_connect"))
    )
    (net (code "60") (name "unconnected-(U2-TDO-Pad39)") (class "Default")
      (node (ref "U2") (pin "39") (pinfunction "TDO_39") (pintype "passive"))
    )
    (net (code "61") (name "unconnected-(U2-TMS-Pad34)") (class "Default")
      (node (ref "U2") (pin "34") (pinfunction "TMS_34") (pintype "passive+no_connect"))
    )
    (net (code "62") (name "unconnected-(U2-TRST-Pad40)") (class "Default")
      (node (ref "U2") (pin "40") (pinfunction "TRST_40") (pintype "passive+no_connect"))
    )
  )
)
